# Test_Board.net
KiCad netlist of a schematic drawn in Altium Designer
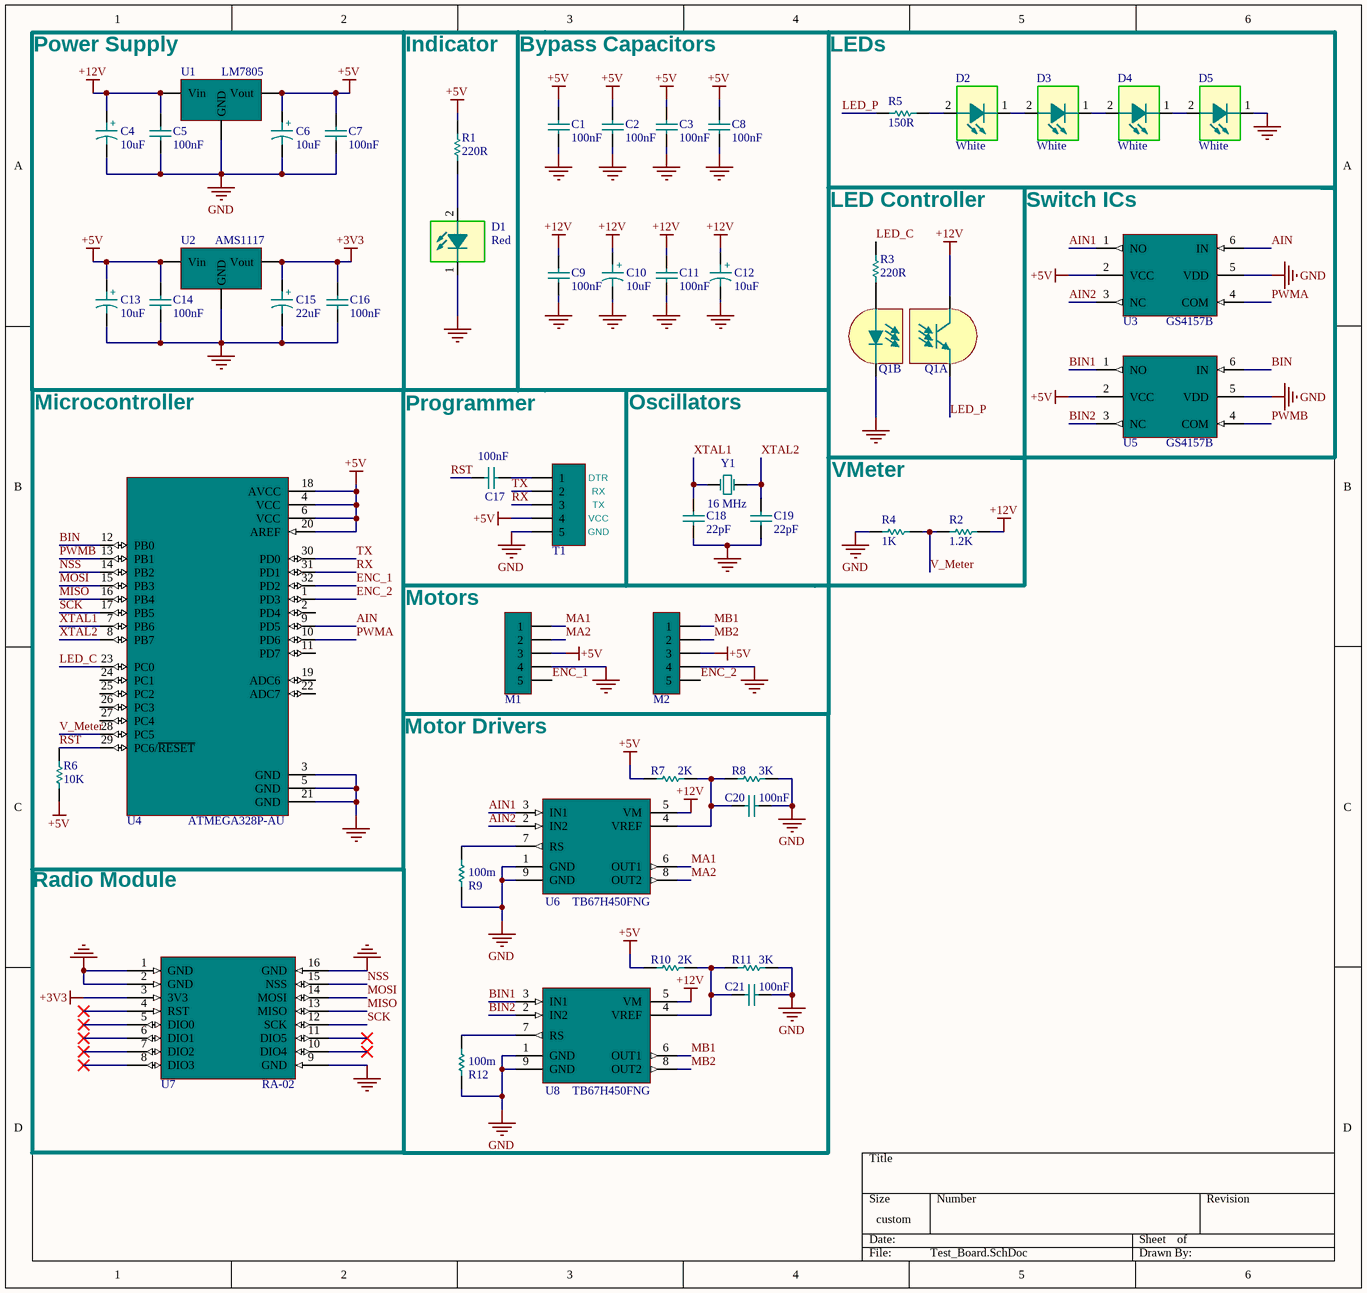
[diagram p0: Test_Board.SchDoc]

(export (version "E")
  (design (tool "Eeschema 10.0.6"))
  (components
    (comp (ref "C1")
      (value "Cap")
      (footprint "CAP 1206")
      (description "AVCC Cap")
      (fields (field (name "VAL-1") "100nF"))
      (libsource (lib "Throwbot") (part "Cap"))
    )
    (comp (ref "C2")
      (value "Cap")
      (footprint "CAP 1206")
      (description "VCC Cap")
      (fields (field (name "VAL-1") "100nF"))
      (libsource (lib "Throwbot") (part "Cap"))
    )
    (comp (ref "C3")
      (value "Cap")
      (footprint "CAP 1206")
      (description "VCC Cap")
      (fields (field (name "VAL-1") "100nF"))
      (libsource (lib "Throwbot") (part "Cap"))
    )
    (comp (ref "C4")
      (value "Cap BiPolar")
      (footprint "CAP Tantalum Size B")
      (description "5V Regulator Cap 10uF 25V")
      (fields (field (name "VAL-1") "10uF"))
      (libsource (lib "Throwbot") (part "Cap BiPolar"))
    )
    (comp (ref "C5")
      (value "Cap")
      (footprint "CAP 1206")
      (description "5V Regulator Cap 100nF")
      (fields (field (name "VAL-1") "100nF"))
      (libsource (lib "Throwbot") (part "Cap"))
    )
    (comp (ref "C6")
      (value "Cap BiPolar")
      (footprint "CAP Tantalum Size B")
      (description "5V Regulator Cap 10uF 25V")
      (fields (field (name "VAL-1") "10uF"))
      (libsource (lib "Throwbot") (part "Cap BiPolar"))
    )
    (comp (ref "C7")
      (value "Cap")
      (footprint "CAP 1206")
      (description "5V Regulator Cap 100nF")
      (fields (field (name "VAL-1") "100nF"))
      (libsource (lib "Throwbot") (part "Cap"))
    )
    (comp (ref "C8")
      (value "Cap")
      (footprint "CAP 1206")
      (description "AREF Cap")
      (fields (field (name "VAL-1") "100nF"))
      (libsource (lib "Throwbot") (part "Cap"))
    )
    (comp (ref "C9")
      (value "Cap")
      (footprint "CAP 1206")
      (description "Motor Power Cap")
      (fields (field (name "VAL-1") "100nF"))
      (libsource (lib "Throwbot") (part "Cap"))
    )
    (comp (ref "C10")
      (value "Cap BiPolar")
      (footprint "CAP Tantalum Size B")
      (description "Motor Power Cap")
      (fields (field (name "VAL-1") "10uF"))
      (libsource (lib "Throwbot") (part "Cap BiPolar"))
    )
    (comp (ref "C11")
      (value "Cap")
      (footprint "CAP 1206")
      (description "Motor Power Cap")
      (fields (field (name "VAL-1") "100nF"))
      (libsource (lib "Throwbot") (part "Cap"))
    )
    (comp (ref "C12")
      (value "Cap BiPolar")
      (footprint "CAP Tantalum Size B")
      (description "Motor Power Cap")
      (fields (field (name "VAL-1") "10uF"))
      (libsource (lib "Throwbot") (part "Cap BiPolar"))
    )
    (comp (ref "C13")
      (value "Cap BiPolar")
      (footprint "CAP Tantalum Size B")
      (description "3.3V Regulator Cap")
      (fields (field (name "VAL-1") "10uF"))
      (libsource (lib "Throwbot") (part "Cap BiPolar"))
    )
    (comp (ref "C14")
      (value "Cap")
      (footprint "CAP 1206")
      (description "3.3V Regulator Cap")
      (fields (field (name "VAL-1") "100nF"))
      (libsource (lib "Throwbot") (part "Cap"))
    )
    (comp (ref "C15")
      (value "Cap BiPolar")
      (footprint "CAP Tantalum Size B")
      (description "3.3V Regulator Cap")
      (fields (field (name "VAL-1") "22uF"))
      (libsource (lib "Throwbot") (part "Cap BiPolar"))
    )
    (comp (ref "C16")
      (value "Cap")
      (footprint "CAP 1206")
      (description "3.3V Regulator Cap")
      (fields (field (name "VAL-1") "100nF"))
      (libsource (lib "Throwbot") (part "Cap"))
    )
    (comp (ref "C17")
      (value "Cap")
      (footprint "CAP 1206")
      (description "Programmer Cap")
      (fields (field (name "VAL-1") "100nF"))
      (libsource (lib "Throwbot") (part "Cap"))
    )
    (comp (ref "C18")
      (value "Cap")
      (footprint "CAP 1206")
      (description "1206 Capacitor")
      (fields (field (name "VAL-2") "22pF"))
      (libsource (lib "Throwbot") (part "Cap"))
    )
    (comp (ref "C19")
      (value "Cap")
      (footprint "CAP 1206")
      (description "1206 Capacitor")
      (fields (field (name "VAL-2") "22pF"))
      (libsource (lib "Throwbot") (part "Cap"))
    )
    (comp (ref "C20")
      (value "Cap")
      (footprint "CAP 1206")
      (description "Motor Driver Cap")
      (fields (field (name "VAL-1") "100nF"))
      (libsource (lib "Throwbot") (part "Cap"))
    )
    (comp (ref "C21")
      (value "Cap")
      (footprint "CAP 1206")
      (description "Motor Driver Cap")
      (fields (field (name "VAL-1") "100nF"))
      (libsource (lib "Throwbot") (part "Cap"))
    )
    (comp (ref "D1")
      (value "LED")
      (footprint "LED 1206")
      (fields (field (name "COLOR-2") "Red"))
      (libsource (lib "") (part "LED_1"))
    )
    (comp (ref "D2")
      (value "LED")
      (footprint "LED 3528")
      (fields (field (name "COLOR-4") "White"))
      (libsource (lib "Throwbot") (part "LED"))
    )
    (comp (ref "D3")
      (value "LED")
      (footprint "LED 3528")
      (fields (field (name "COLOR-4") "White"))
      (libsource (lib "Throwbot") (part "LED"))
    )
    (comp (ref "D4")
      (value "LED")
      (footprint "LED 3528")
      (fields (field (name "COLOR-4") "White"))
      (libsource (lib "Throwbot") (part "LED"))
    )
    (comp (ref "D5")
      (value "LED")
      (footprint "LED 3528")
      (fields (field (name "COLOR-4") "White"))
      (libsource (lib "Throwbot") (part "LED"))
    )
    (comp (ref "M1") (value "Motor") (footprint "Motor") (libsource (lib "Throwbot") (part "Motor")))
    (comp (ref "M2") (value "Motor") (footprint "Motor") (libsource (lib "Throwbot") (part "Motor")))
    (comp (ref "Q1")
      (value "PC817")
      (footprint "PC817")
      (description "DIP 4pin General Purpose  Photocoupler")
      (libsource (lib "Throwbot") (part "PC817"))
    )
    (comp (ref "R1")
      (value "Resistor")
      (footprint "RES 1206")
      (fields (field (name "VAL-3") "220R"))
      (libsource (lib "Throwbot") (part "Resistor"))
    )
    (comp (ref "R2")
      (value "Resistor")
      (footprint "RES 1206")
      (fields (field (name "VAL-12") "1.2K"))
      (libsource (lib "Throwbot") (part "Resistor"))
    )
    (comp (ref "R3")
      (value "Resistor")
      (footprint "RES 1206")
      (fields (field (name "VAL-3") "220R"))
      (libsource (lib "Throwbot") (part "Resistor"))
    )
    (comp (ref "R4")
      (value "Resistor")
      (footprint "RES 1206")
      (fields (field (name "VAL-1") "1K"))
      (libsource (lib "Throwbot") (part "Resistor"))
    )
    (comp (ref "R5")
      (value "Resistor")
      (footprint "RES 1206")
      (fields (field (name "VAL-8") "150R"))
      (libsource (lib "Throwbot") (part "Resistor"))
    )
    (comp (ref "R6")
      (value "Resistor")
      (footprint "RES 1206")
      (fields (field (name "VAL-2") "10K"))
      (libsource (lib "Throwbot") (part "Resistor"))
    )
    (comp (ref "R7")
      (value "Resistor")
      (footprint "RES 1206")
      (fields (field (name "VAL-11") "2K"))
      (libsource (lib "Throwbot") (part "Resistor"))
    )
    (comp (ref "R8")
      (value "Resistor")
      (footprint "RES 1206")
      (fields (field (name "VAL-10") "3K"))
      (libsource (lib "Throwbot") (part "Resistor"))
    )
    (comp (ref "R9")
      (value "Resistor")
      (footprint "RES 1206")
      (fields (field (name "VAL-9") "100m"))
      (libsource (lib "Throwbot") (part "Resistor"))
    )
    (comp (ref "R10")
      (value "Resistor")
      (footprint "RES 1206")
      (fields (field (name "VAL-11") "2K"))
      (libsource (lib "Throwbot") (part "Resistor"))
    )
    (comp (ref "R11")
      (value "Resistor")
      (footprint "RES 1206")
      (fields (field (name "VAL-10") "3K"))
      (libsource (lib "Throwbot") (part "Resistor"))
    )
    (comp (ref "R12")
      (value "Resistor")
      (footprint "RES 1206")
      (fields (field (name "VAL-9") "100m"))
      (libsource (lib "Throwbot") (part "Resistor"))
    )
    (comp (ref "T1")
      (value "5 Pin Socket")
      (footprint "MO Header 5")
      (libsource (lib "Throwbot") (part "5 Pin Socket"))
    )
    (comp (ref "U1")
      (value "LM7805")
      (footprint "7805 SMD")
      (description "5V Regulator")
      (libsource (lib "Throwbot") (part "LM7805"))
    )
    (comp (ref "U2")
      (value "AMS1117")
      (footprint "AMS1117")
      (description "3V3 Regulator")
      (libsource (lib "Throwbot") (part "AMS1117"))
    )
    (comp (ref "U3") (value "GS4157B") (footprint "GS4157B") (libsource (lib "Throwbot") (part "GS4157B")))
    (comp (ref "U4")
      (value "ATMEGA328P-AU")
      (footprint "ATmega328")
      (description "ATmega 328 Microcontroller")
      (libsource (lib "Throwbot") (part "ATMEGA328P-AU"))
    )
    (comp (ref "U5") (value "GS4157B") (footprint "GS4157B") (libsource (lib "Throwbot") (part "GS4157B")))
    (comp (ref "U6")
      (value "TB67H450FNG")
      (footprint "TB67H450FNG")
      (description "Motor Driver")
      (libsource (lib "Throwbot") (part "TB67H450FNG"))
    )
    (comp (ref "U7")
      (value "RA-02")
      (footprint "RA-02")
      (description "LoRa RA-02")
      (libsource (lib "Throwbot") (part "RA-02"))
    )
    (comp (ref "U8")
      (value "TB67H450FNG")
      (footprint "TB67H450FNG")
      (description "Motor Driver")
      (libsource (lib "Throwbot") (part "TB67H450FNG"))
    )
    (comp (ref "Y1")
      (value "XTAL")
      (footprint "Crystal-5032")
      (description "XTAL Crystal")
      (fields (field (name "VAL-2") "16 MHz"))
      (libsource (lib "Throwbot") (part "XTAL"))
    )
  )
  (nets
    (net (code "1") (name "+3V3") (class "Default")
      (node (ref "C15") (pin "1") (pinfunction "1_1") (pintype "passive"))
      (node (ref "C16") (pin "1") (pinfunction "1_1") (pintype "passive"))
      (node (ref "U2") (pin "2") (pinfunction "Vout_2") (pintype "power_in"))
      (node (ref "U7") (pin "3") (pinfunction "3V3_3") (pintype "input"))
    )
    (net (code "2") (name "+5V") (class "Default")
      (node (ref "C1") (pin "1") (pinfunction "1_1") (pintype "passive"))
      (node (ref "C13") (pin "1") (pinfunction "1_1") (pintype "passive"))
      (node (ref "C14") (pin "1") (pinfunction "1_1") (pintype "passive"))
      (node (ref "C2") (pin "1") (pinfunction "1_1") (pintype "passive"))
      (node (ref "C3") (pin "1") (pinfunction "1_1") (pintype "passive"))
      (node (ref "C6") (pin "1") (pinfunction "1_1") (pintype "passive"))
      (node (ref "C7") (pin "1") (pinfunction "1_1") (pintype "passive"))
      (node (ref "C8") (pin "1") (pinfunction "1_1") (pintype "passive"))
      (node (ref "M1") (pin "3") (pinfunction "3_3") (pintype "passive"))
      (node (ref "M2") (pin "3") (pinfunction "3_3") (pintype "passive"))
      (node (ref "R1") (pin "2") (pinfunction "2_2") (pintype "passive"))
      (node (ref "R10") (pin "2") (pinfunction "2_2") (pintype "passive"))
      (node (ref "R6") (pin "2") (pinfunction "2_2") (pintype "passive"))
      (node (ref "R7") (pin "2") (pinfunction "2_2") (pintype "passive"))
      (node (ref "T1") (pin "4") (pinfunction "4_4") (pintype "passive"))
      (node (ref "U1") (pin "3") (pinfunction "Vout_3") (pintype "power_in"))
      (node (ref "U2") (pin "3") (pinfunction "Vin_3") (pintype "power_in"))
      (node (ref "U3") (pin "2") (pinfunction "VCC_2") (pintype "power_in"))
      (node (ref "U4") (pin "18") (pinfunction "AVCC_18") (pintype "power_in"))
      (node (ref "U4") (pin "20") (pinfunction "AREF_20") (pintype "input"))
      (node (ref "U4") (pin "4") (pinfunction "VCC_4") (pintype "power_in"))
      (node (ref "U4") (pin "6") (pinfunction "VCC_6") (pintype "power_in"))
      (node (ref "U5") (pin "2") (pinfunction "VCC_2") (pintype "power_in"))
    )
    (net (code "3") (name "+12V") (class "Default")
      (node (ref "C10") (pin "1") (pinfunction "1_1") (pintype "passive"))
      (node (ref "C11") (pin "1") (pinfunction "1_1") (pintype "passive"))
      (node (ref "C12") (pin "1") (pinfunction "1_1") (pintype "passive"))
      (node (ref "C4") (pin "1") (pinfunction "1_1") (pintype "passive"))
      (node (ref "C5") (pin "1") (pinfunction "1_1") (pintype "passive"))
      (node (ref "C9") (pin "1") (pinfunction "1_1") (pintype "passive"))
      (node (ref "Q1") (pin "4") (pinfunction "C_4") (pintype "passive"))
      (node (ref "R2") (pin "2") (pinfunction "2_2") (pintype "passive"))
      (node (ref "U1") (pin "1") (pinfunction "Vin_1") (pintype "power_in"))
      (node (ref "U6") (pin "5") (pinfunction "VM_5") (pintype "power_in"))
      (node (ref "U8") (pin "5") (pinfunction "VM_5") (pintype "power_in"))
    )
    (net (code "4") (name "/AIN") (class "Default")
      (node (ref "U3") (pin "6") (pinfunction "IN_6") (pintype "input"))
      (node (ref "U4") (pin "9") (pinfunction "PD5_9") (pintype "bidirectional"))
    )
    (net (code "5") (name "/AIN1") (class "Default")
      (node (ref "U3") (pin "1") (pinfunction "NO_1") (pintype "output"))
      (node (ref "U6") (pin "3") (pinfunction "IN1_3") (pintype "input"))
    )
    (net (code "6") (name "/AIN2") (class "Default")
      (node (ref "U3") (pin "3") (pinfunction "NC_3") (pintype "output"))
      (node (ref "U6") (pin "2") (pinfunction "IN2_2") (pintype "input"))
    )
    (net (code "7") (name "/BIN") (class "Default")
      (node (ref "U4") (pin "12") (pinfunction "PB0_12") (pintype "bidirectional"))
      (node (ref "U5") (pin "6") (pinfunction "IN_6") (pintype "input"))
    )
    (net (code "8") (name "/BIN1") (class "Default")
      (node (ref "U5") (pin "1") (pinfunction "NO_1") (pintype "output"))
      (node (ref "U8") (pin "3") (pinfunction "IN1_3") (pintype "input"))
    )
    (net (code "9") (name "/BIN2") (class "Default")
      (node (ref "U5") (pin "3") (pinfunction "NC_3") (pintype "output"))
      (node (ref "U8") (pin "2") (pinfunction "IN2_2") (pintype "input"))
    )
    (net (code "10") (name "/ENC_1") (class "Default")
      (node (ref "M1") (pin "5") (pinfunction "5_5") (pintype "passive"))
      (node (ref "U4") (pin "32") (pinfunction "PD2_32") (pintype "bidirectional"))
    )
    (net (code "11") (name "/ENC_2") (class "Default")
      (node (ref "M2") (pin "5") (pinfunction "5_5") (pintype "passive"))
      (node (ref "U4") (pin "1") (pinfunction "PD3_1") (pintype "bidirectional"))
    )
    (net (code "12") (name "/LED_C") (class "Default")
      (node (ref "R3") (pin "2") (pinfunction "2_2") (pintype "passive"))
      (node (ref "U4") (pin "23") (pinfunction "PC0_23") (pintype "bidirectional"))
    )
    (net (code "13") (name "/LED_P") (class "Default")
      (node (ref "Q1") (pin "3") (pinfunction "E_3") (pintype "passive"))
      (node (ref "R5") (pin "2") (pinfunction "2_2") (pintype "passive"))
    )
    (net (code "14") (name "/MA1") (class "Default")
      (node (ref "M1") (pin "1") (pinfunction "1_1") (pintype "passive"))
      (node (ref "U6") (pin "6") (pinfunction "OUT1_6") (pintype "output"))
    )
    (net (code "15") (name "/MA2") (class "Default")
      (node (ref "M1") (pin "2") (pinfunction "2_2") (pintype "passive"))
      (node (ref "U6") (pin "8") (pinfunction "OUT2_8") (pintype "output"))
    )
    (net (code "16") (name "/MB1") (class "Default")
      (node (ref "M2") (pin "1") (pinfunction "1_1") (pintype "passive"))
      (node (ref "U8") (pin "6") (pinfunction "OUT1_6") (pintype "output"))
    )
    (net (code "17") (name "/MB2") (class "Default")
      (node (ref "M2") (pin "2") (pinfunction "2_2") (pintype "passive"))
      (node (ref "U8") (pin "8") (pinfunction "OUT2_8") (pintype "output"))
    )
    (net (code "18") (name "/MISO") (class "Default")
      (node (ref "U4") (pin "16") (pinfunction "PB4_16") (pintype "bidirectional"))
      (node (ref "U7") (pin "13") (pinfunction "MISO_13") (pintype "bidirectional"))
    )
    (net (code "19") (name "/MOSI") (class "Default")
      (node (ref "U4") (pin "15") (pinfunction "PB3_15") (pintype "bidirectional"))
      (node (ref "U7") (pin "14") (pinfunction "MOSI_14") (pintype "bidirectional"))
    )
    (net (code "20") (name "/NSS") (class "Default")
      (node (ref "U4") (pin "14") (pinfunction "PB2_14") (pintype "bidirectional"))
      (node (ref "U7") (pin "15") (pinfunction "NSS_15") (pintype "bidirectional"))
    )
    (net (code "21") (name "/PWMA") (class "Default")
      (node (ref "U3") (pin "4") (pinfunction "COM_4") (pintype "input"))
      (node (ref "U4") (pin "10") (pinfunction "PD6_10") (pintype "bidirectional"))
    )
    (net (code "22") (name "/PWMB") (class "Default")
      (node (ref "U4") (pin "13") (pinfunction "PB1_13") (pintype "bidirectional"))
      (node (ref "U5") (pin "4") (pinfunction "COM_4") (pintype "input"))
    )
    (net (code "23") (name "/RST") (class "Default")
      (node (ref "C17") (pin "1") (pinfunction "1_1") (pintype "passive"))
      (node (ref "R6") (pin "1") (pinfunction "1_1") (pintype "passive"))
      (node (ref "U4") (pin "29") (pinfunction "PC6/~{RESET}_29") (pintype "bidirectional"))
    )
    (net (code "24") (name "/RX") (class "Default")
      (node (ref "T1") (pin "3") (pinfunction "3_3") (pintype "passive"))
      (node (ref "U4") (pin "31") (pinfunction "PD1_31") (pintype "bidirectional"))
    )
    (net (code "25") (name "/SCK") (class "Default")
      (node (ref "U4") (pin "17") (pinfunction "PB5_17") (pintype "bidirectional"))
      (node (ref "U7") (pin "12") (pinfunction "SCK_12") (pintype "bidirectional"))
    )
    (net (code "26") (name "/TX") (class "Default")
      (node (ref "T1") (pin "2") (pinfunction "2_2") (pintype "passive"))
      (node (ref "U4") (pin "30") (pinfunction "PD0_30") (pintype "bidirectional"))
    )
    (net (code "27") (name "/V_Meter") (class "Default")
      (node (ref "R2") (pin "1") (pinfunction "1_1") (pintype "passive"))
      (node (ref "R4") (pin "2") (pinfunction "2_2") (pintype "passive"))
      (node (ref "U4") (pin "28") (pinfunction "PC5_28") (pintype "bidirectional"))
    )
    (net (code "28") (name "/XTAL1") (class "Default")
      (node (ref "C18") (pin "2") (pinfunction "2_2") (pintype "passive"))
      (node (ref "U4") (pin "7") (pinfunction "PB6_7") (pintype "bidirectional"))
      (node (ref "Y1") (pin "1") (pinfunction "OSC1_1") (pintype "passive"))
    )
    (net (code "29") (name "/XTAL2") (class "Default")
      (node (ref "C19") (pin "2") (pinfunction "2_2") (pintype "passive"))
      (node (ref "U4") (pin "8") (pinfunction "PB7_8") (pintype "bidirectional"))
      (node (ref "Y1") (pin "2") (pinfunction "OSC2_2") (pintype "passive"))
    )
    (net (code "30") (name "GND") (class "Default")
      (node (ref "C1") (pin "2") (pinfunction "2_2") (pintype "passive"))
      (node (ref "C10") (pin "2") (pinfunction "2_2") (pintype "passive"))
      (node (ref "C11") (pin "2") (pinfunction "2_2") (pintype "passive"))
      (node (ref "C12") (pin "2") (pinfunction "2_2") (pintype "passive"))
      (node (ref "C13") (pin "2") (pinfunction "2_2") (pintype "passive"))
      (node (ref "C14") (pin "2") (pinfunction "2_2") (pintype "passive"))
      (node (ref "C15") (pin "2") (pinfunction "2_2") (pintype "passive"))
      (node (ref "C16") (pin "2") (pinfunction "2_2") (pintype "passive"))
      (node (ref "C18") (pin "1") (pinfunction "1_1") (pintype "passive"))
      (node (ref "C19") (pin "1") (pinfunction "1_1") (pintype "passive"))
      (node (ref "C2") (pin "2") (pinfunction "2_2") (pintype "passive"))
      (node (ref "C20") (pin "2") (pinfunction "2_2") (pintype "passive"))
      (node (ref "C21") (pin "2") (pinfunction "2_2") (pintype "passive"))
      (node (ref "C3") (pin "2") (pinfunction "2_2") (pintype "passive"))
      (node (ref "C4") (pin "2") (pinfunction "2_2") (pintype "passive"))
      (node (ref "C5") (pin "2") (pinfunction "2_2") (pintype "passive"))
      (node (ref "C6") (pin "2") (pinfunction "2_2") (pintype "passive"))
      (node (ref "C7") (pin "2") (pinfunction "2_2") (pintype "passive"))
      (node (ref "C8") (pin "2") (pinfunction "2_2") (pintype "passive"))
      (node (ref "C9") (pin "2") (pinfunction "2_2") (pintype "passive"))
      (node (ref "D1") (pin "1") (pinfunction "1_1") (pintype "passive"))
      (node (ref "D5") (pin "1") (pinfunction "1_1") (pintype "passive"))
      (node (ref "M1") (pin "4") (pinfunction "4_4") (pintype "passive"))
      (node (ref "M2") (pin "4") (pinfunction "4_4") (pintype "passive"))
      (node (ref "Q1") (pin "2") (pinfunction "K_2") (pintype "passive"))
      (node (ref "R11") (pin "1") (pinfunction "1_1") (pintype "passive"))
      (node (ref "R12") (pin "1") (pinfunction "1_1") (pintype "passive"))
      (node (ref "R4") (pin "1") (pinfunction "1_1") (pintype "passive"))
      (node (ref "R8") (pin "1") (pinfunction "1_1") (pintype "passive"))
      (node (ref "R9") (pin "1") (pinfunction "1_1") (pintype "passive"))
      (node (ref "T1") (pin "5") (pinfunction "5_5") (pintype "passive"))
      (node (ref "U1") (pin "2") (pinfunction "GND_2") (pintype "power_in"))
      (node (ref "U2") (pin "1") (pinfunction "GND_1") (pintype "power_in"))
      (node (ref "U3") (pin "5") (pinfunction "VDD_5") (pintype "power_in"))
      (node (ref "U4") (pin "21") (pinfunction "GND_21") (pintype "power_in"))
      (node (ref "U4") (pin "3") (pinfunction "GND_3") (pintype "power_in"))
      (node (ref "U4") (pin "5") (pinfunction "GND_5") (pintype "power_in"))
      (node (ref "U5") (pin "5") (pinfunction "VDD_5") (pintype "power_in"))
      (node (ref "U6") (pin "1") (pinfunction "GND_1") (pintype "power_in"))
      (node (ref "U6") (pin "9") (pinfunction "GND_9") (pintype "power_in"))
      (node (ref "U7") (pin "1") (pinfunction "GND_1") (pintype "input"))
      (node (ref "U7") (pin "16") (pinfunction "GND_16") (pintype "input"))
      (node (ref "U7") (pin "2") (pinfunction "GND_2") (pintype "input"))
      (node (ref "U7") (pin "9") (pinfunction "GND_9") (pintype "input"))
      (node (ref "U8") (pin "1") (pinfunction "GND_1") (pintype "power_in"))
      (node (ref "U8") (pin "9") (pinfunction "GND_9") (pintype "power_in"))
    )
    (net (code "31") (name "Net-(C17-Pad2)") (class "Default")
      (node (ref "C17") (pin "2") (pinfunction "2_2") (pintype "passive"))
      (node (ref "T1") (pin "1") (pinfunction "1_1") (pintype "passive"))
    )
    (net (code "32") (name "Net-(D1-Pad2)") (class "Default")
      (node (ref "D1") (pin "2") (pinfunction "2_2") (pintype "passive"))
      (node (ref "R1") (pin "1") (pinfunction "1_1") (pintype "passive"))
    )
    (net (code "33") (name "Net-(D2-Pad1)") (class "Default")
      (node (ref "D2") (pin "1") (pinfunction "1_1") (pintype "passive"))
      (node (ref "D3") (pin "2") (pinfunction "2_2") (pintype "passive"))
    )
    (net (code "34") (name "Net-(D2-Pad2)") (class "Default")
      (node (ref "D2") (pin "2") (pinfunction "2_2") (pintype "passive"))
      (node (ref "R5") (pin "1") (pinfunction "1_1") (pintype "passive"))
    )
    (net (code "35") (name "Net-(D3-Pad1)") (class "Default")
      (node (ref "D3") (pin "1") (pinfunction "1_1") (pintype "passive"))
      (node (ref "D4") (pin "2") (pinfunction "2_2") (pintype "passive"))
    )
    (net (code "36") (name "Net-(D4-Pad1)") (class "Default")
      (node (ref "D4") (pin "1") (pinfunction "1_1") (pintype "passive"))
      (node (ref "D5") (pin "2") (pinfunction "2_2") (pintype "passive"))
    )
    (net (code "37") (name "Net-(Q1B-A)") (class "Default")
      (node (ref "Q1") (pin "1") (pinfunction "A_1") (pintype "passive"))
      (node (ref "R3") (pin "1") (pinfunction "1_1") (pintype "passive"))
    )
    (net (code "38") (name "Net-(U6-RS)") (class "Default")
      (node (ref "R9") (pin "2") (pinfunction "2_2") (pintype "passive"))
      (node (ref "U6") (pin "7") (pinfunction "RS_7") (pintype "output"))
    )
    (net (code "39") (name "Net-(U6-VREF)") (class "Default")
      (node (ref "C20") (pin "1") (pinfunction "1_1") (pintype "passive"))
      (node (ref "R7") (pin "1") (pinfunction "1_1") (pintype "passive"))
      (node (ref "R8") (pin "2") (pinfunction "2_2") (pintype "passive"))
      (node (ref "U6") (pin "4") (pinfunction "VREF_4") (pintype "power_in"))
    )
    (net (code "40") (name "Net-(U8-RS)") (class "Default")
      (node (ref "R12") (pin "2") (pinfunction "2_2") (pintype "passive"))
      (node (ref "U8") (pin "7") (pinfunction "RS_7") (pintype "output"))
    )
    (net (code "41") (name "Net-(U8-VREF)") (class "Default")
      (node (ref "C21") (pin "1") (pinfunction "1_1") (pintype "passive"))
      (node (ref "R10") (pin "1") (pinfunction "1_1") (pintype "passive"))
      (node (ref "R11") (pin "2") (pinfunction "2_2") (pintype "passive"))
      (node (ref "U8") (pin "4") (pinfunction "VREF_4") (pintype "power_in"))
    )
    (net (code "42") (name "unconnected-(U4-ADC6-Pad19)") (class "Default")
      (node (ref "U4") (pin "19") (pinfunction "ADC6_19") (pintype "bidirectional"))
    )
    (net (code "43") (name "unconnected-(U4-ADC7-Pad22)") (class "Default")
      (node (ref "U4") (pin "22") (pinfunction "ADC7_22") (pintype "bidirectional"))
    )
    (net (code "44") (name "unconnected-(U4-PC1-Pad24)") (class "Default")
      (node (ref "U4") (pin "24") (pinfunction "PC1_24") (pintype "bidirectional"))
    )
    (net (code "45") (name "unconnected-(U4-PC2-Pad25)") (class "Default")
      (node (ref "U4") (pin "25") (pinfunction "PC2_25") (pintype "bidirectional"))
    )
    (net (code "46") (name "unconnected-(U4-PC3-Pad26)") (class "Default")
      (node (ref "U4") (pin "26") (pinfunction "PC3_26") (pintype "bidirectional"))
    )
    (net (code "47") (name "unconnected-(U4-PC4-Pad27)") (class "Default")
      (node (ref "U4") (pin "27") (pinfunction "PC4_27") (pintype "bidirectional"))
    )
    (net (code "48") (name "unconnected-(U4-PD4-Pad2)") (class "Default")
      (node (ref "U4") (pin "2") (pinfunction "PD4_2") (pintype "bidirectional"))
    )
    (net (code "49") (name "unconnected-(U4-PD7-Pad11)") (class "Default")
      (node (ref "U4") (pin "11") (pinfunction "PD7_11") (pintype "bidirectional"))
    )
    (net (code "50") (name "unconnected-(U7-DIO0-Pad5)") (class "Default")
      (node (ref "U7") (pin "5") (pinfunction "DIO0_5") (pintype "bidirectional+no_connect"))
    )
    (net (code "51") (name "unconnected-(U7-DIO1-Pad6)") (class "Default")
      (node (ref "U7") (pin "6") (pinfunction "DIO1_6") (pintype "bidirectional+no_connect"))
    )
    (net (code "52") (name "unconnected-(U7-DIO2-Pad7)") (class "Default")
      (node (ref "U7") (pin "7") (pinfunction "DIO2_7") (pintype "bidirectional+no_connect"))
    )
    (net (code "53") (name "unconnected-(U7-DIO3-Pad8)") (class "Default")
      (node (ref "U7") (pin "8") (pinfunction "DIO3_8") (pintype "bidirectional+no_connect"))
    )
    (net (code "54") (name "unconnected-(U7-DIO4-Pad10)") (class "Default")
      (node (ref "U7") (pin "10") (pinfunction "DIO4_10") (pintype "bidirectional+no_connect"))
    )
    (net (code "55") (name "unconnected-(U7-DIO5-Pad11)") (class "Default")
      (node (ref "U7") (pin "11") (pinfunction "DIO5_11") (pintype "bidirectional+no_connect"))
    )
    (net (code "56") (name "unconnected-(U7-RST-Pad4)") (class "Default")
      (node (ref "U7") (pin "4") (pinfunction "RST_4") (pintype "input+no_connect"))
    )
  )
)
